# Power.net
KiCad netlist of a schematic drawn in Altium Designer
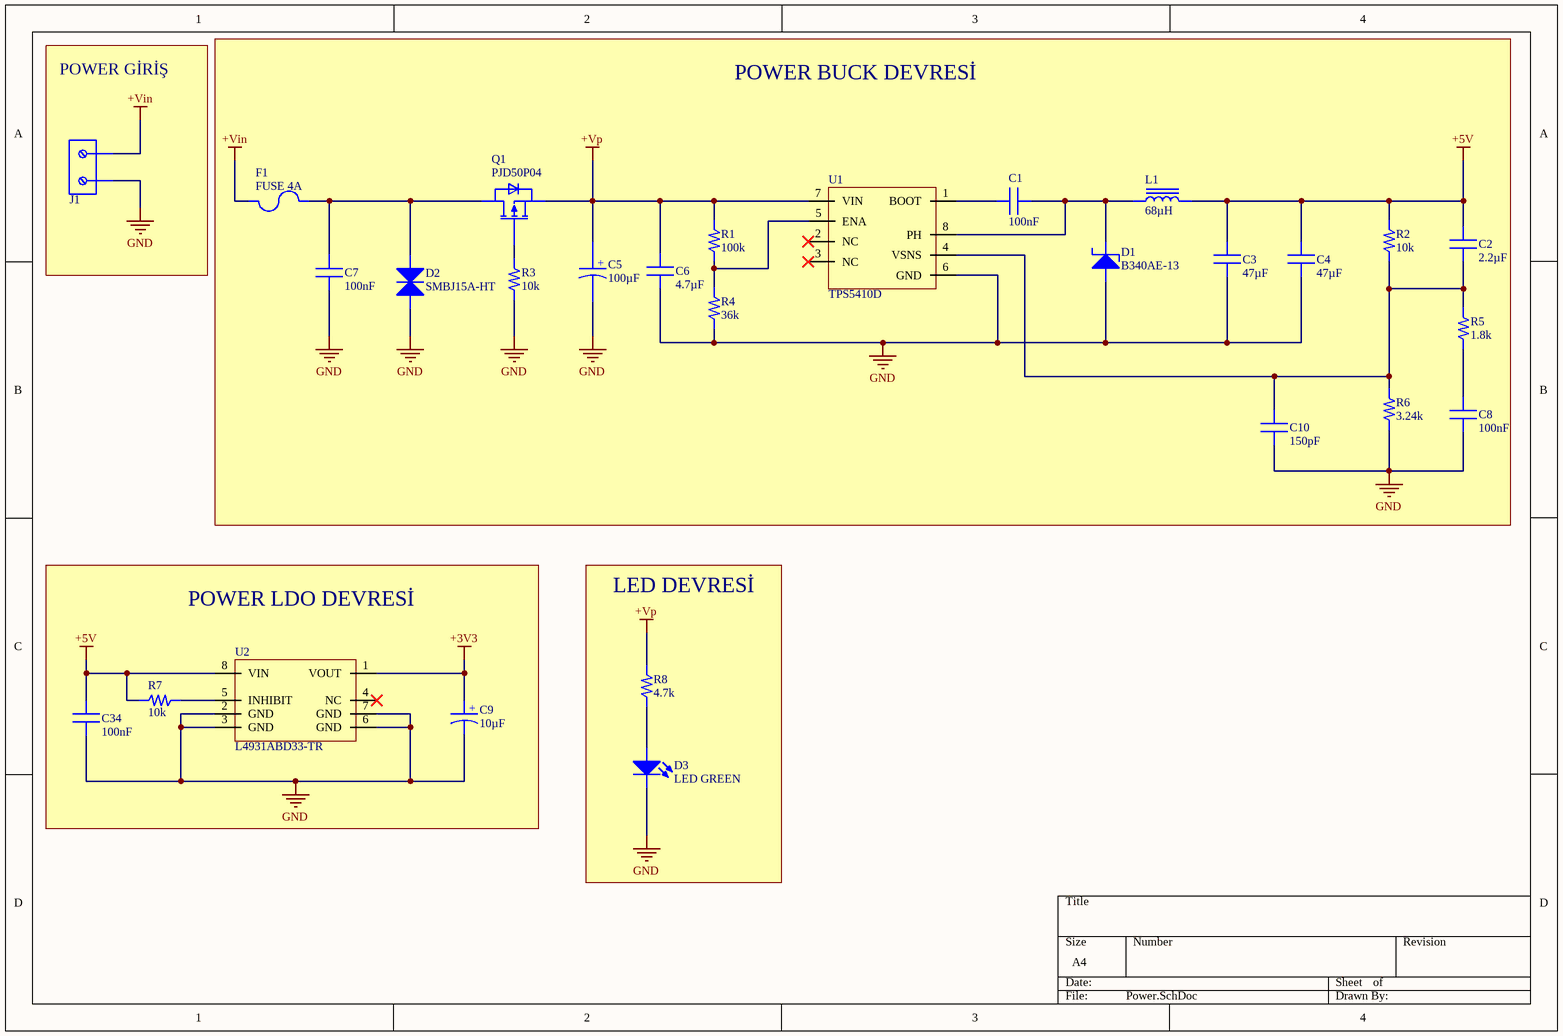
[diagram p0: Power.SchDoc]

(export (version "E")
  (design (tool "Eeschema 10.0.6"))
  (components
    (comp (ref "C1")
      (value "100nF")
      (footprint "CAP 0603 100NF")
      (description "MLCC (1608) 0603 100nF 50VDC ±10% X7R AUTOMOTIVE CL10B104KB85PNC")
      (fields (field (name "MANUFACTURER") "SAMSUNG") (field (name "TOLERANCE") "±10 %"))
      (libsource (lib "Motor Controller SchLib") (part "CAP 0603 100nF"))
    )
    (comp (ref "C2")
      (value "2.2µF")
      (footprint "CAP 0603 2.2uF")
      (description "MLCC (1608) 0603 2.2uF 16VDC ±10% X5R CL10A225KO8NNNC")
      (fields (field (name "TOLERANCE") "±10 %") (field (name "MANUFACTURER") "SAMSUNG"))
      (libsource (lib "Motor Controller SchLib") (part "CAP 0603 2.2uF"))
    )
    (comp (ref "C3")
      (value "47µF")
      (footprint "CL32A476KOJNNNE")
      (description "MLCC 1210 47uF 16VDC ±10% X5R   CL32A476KOJNNNE")
      (fields (field (name "MANUFACTURER") "SAMSUNG") (field (name "TOLERANCE") "±10 %"))
      (libsource (lib "Motor Controller SchLib") (part "CAP 1210 47µF"))
    )
    (comp (ref "C4")
      (value "47µF")
      (footprint "CL32A476KOJNNNE")
      (description "MLCC 1210 47uF 16VDC ±10% X5R   CL32A476KOJNNNE")
      (fields (field (name "MANUFACTURER") "SAMSUNG") (field (name "TOLERANCE") "±10 %"))
      (libsource (lib "Motor Controller SchLib") (part "CAP 1210 47µF"))
    )
    (comp (ref "C5")
      (value "100µF")
      (footprint "CAP_EEHZA1H101P")
      (description "CAP.EL.100µF 50V 10.5x10.5 105C SMD")
      (fields (field (name "MANUFACTURER") "Panasonic") (field (name "TOLERANCE") "±20 %"))
      (libsource (lib "Motor Controller SchLib") (part "CAP 100uF"))
    )
    (comp (ref "C6")
      (value "4.7µF")
      (footprint "CAP 0603 4.7uF")
      (description "MLCC (1608) 0603 4.7uF 35VDC ±10% X5R CL10A475KL8NRNC")
      (fields (field (name "MANUFACTURER") "SAMSUNG") (field (name "TOLERANCE") "±10 %"))
      (libsource (lib "Motor Controller SchLib") (part "CAP 0603 4.7uF CL10A475KL8NRNC"))
    )
    (comp (ref "C7")
      (value "100nF")
      (footprint "CAP 0603 100NF")
      (description "MLCC (1608) 0603 100nF 50VDC ±10% X7R AUTOMOTIVE CL10B104KB85PNC")
      (fields (field (name "MANUFACTURER") "SAMSUNG") (field (name "TOLERANCE") "±10 %"))
      (libsource (lib "Motor Controller SchLib") (part "CAP 0603 100nF"))
    )
    (comp (ref "C8")
      (value "100nF")
      (footprint "CAP 0603 100NF")
      (description "MLCC (1608) 0603 100nF 50VDC ±10% X7R AUTOMOTIVE CL10B104KB85PNC")
      (fields (field (name "MANUFACTURER") "SAMSUNG") (field (name "TOLERANCE") "±10 %"))
      (libsource (lib "Motor Controller SchLib") (part "CAP 0603 100nF"))
    )
    (comp (ref "C9")
      (value "10µF")
      (footprint "CAP_EEEFK1H100UR")
      (description "CAP.EL.10uF 50V 5x5.8 105C 2000H AEC-Q200 SMT")
      (fields (field (name "MANUFACTURER") "PANASONIC") (field (name "TOLERANCE") "±20 %"))
      (libsource (lib "Motor Controller SchLib") (part "CAP 10µF Electrolytic"))
    )
    (comp (ref "C10")
      (value "150pF")
      (footprint "CAP 0603 150pF")
      (description "MLCC (1608) 0603 150pF 50VDC ±5% C0G (NP0) CL10C151JB8NNNC")
      (fields (field (name "MANUFACTURER") "SAMSUNG") (field (name "TOLERANCE") "±5 %"))
      (libsource (lib "Motor Controller SchLib") (part "CAP 0603 150pF"))
    )
    (comp (ref "C34")
      (value "100nF")
      (footprint "CAP 0603 100NF")
      (description "MLCC (1608) 0603 100nF 50VDC ±10% X7R AUTOMOTIVE CL10B104KB85PNC")
      (fields (field (name "MANUFACTURER") "SAMSUNG") (field (name "TOLERANCE") "±10 %"))
      (libsource (lib "Motor Controller SchLib") (part "CAP 0603 100nF"))
    )
    (comp (ref "D1")
      (value "B340AE-13")
      (footprint "DIODE B340AE-13")
      (description "DIODE SCHOTTKY 3A 40V SMA DO-214AC")
      (fields (field (name "MANUFACTURER") "DIODES"))
      (libsource (lib "Motor Controller SchLib") (part "DIODE SCHOTTKY B340AE-13"))
    )
    (comp (ref "D2")
      (value "SMBJ15A-HT")
      (footprint "TVS DIODE SMBJ15A")
      (description "DIODE TVS 600W 15V DO214AA SMB")
      (fields (field (name "MANUFACTURER") "HOTTECH"))
      (libsource (lib "Motor Controller SchLib") (part "DIODE TVS SMBJ15A-HT"))
    )
    (comp (ref "D3")
      (value "LED GREEN")
      (footprint "LED GREEN 0603 APT1608CGCK")
      (description "LED GREEN CLEAR CHIP SMD")
      (fields (field (name "MANUFACTURER") "KINGBRIGHT"))
      (libsource (lib "Motor Controller SchLib") (part "SMD LED GREEN APT1608CGCK"))
    )
    (comp (ref "F1")
      (value "FUSE 4A")
      (footprint "FUSE 0805 MFU0805FF04000P100")
      (description "FUSE BOARD MOUNT 0805 4A 32VDC")
      (fields (field (name "MANUFACTURER") "VISHAY"))
      (libsource (lib "Motor Controller SchLib") (part "FUSE"))
    )
    (comp (ref "J1")
      (value "2x1 5mm T.B.")
      (footprint "Terminal Block 2x1")
      (description "TERM.BLK.5.00MM 2P PCB TYPE 0 BOY BLUE")
      (fields (field (name "MANUFACTURER") "DEGSON"))
      (libsource (lib "Motor Controller SchLib") (part "Terminal Block 2x1"))
    )
    (comp (ref "L1")
      (value "68µH")
      (footprint "IND CBC3225T680KR 68uH")
      (description "INDUCTOR FIXED 68UH 10x10mm SMD 744066680")
      (fields (field (name "TOLERANCE") "±30 %") (field (name "MANUFACTURER") "WURTH"))
      (libsource (lib "Motor Controller SchLib") (part "INDUCTOR 68µH SMD 744066680"))
    )
    (comp (ref "Q1")
      (value "PJD50P04")
      (footprint "TO252 (DPAK) IRFR024NTRPBF")
      (description "MOSFET DIS.50A 40V P-CH AUTOMOTIVE TO-252AA SMT")
      (fields (field (name "VOLTAGE") "40 V") (field (name "MANUFACTURER") "PANJIT"))
      (libsource (lib "Motor Controller SchLib") (part "P-CH Mosfet 40V 9A PJD50P04-AU_L2_000A1"))
    )
    (comp (ref "R1")
      (value "100k")
      (footprint "RES 0402 ROYALOHM GENERAL")
      (description "RES.(1005) 0402 100K Ohms 1% 1/16W 100PPM\r\n0402WGF1003TCE")
      (fields (field (name "POWER") "1/16 W") (field (name "TOLERANCE") "±5 %"))
      (libsource (lib "Motor Controller SchLib") (part "RES 0402 100k 0402WGF1003TCE"))
    )
    (comp (ref "R2")
      (value "10k")
      (footprint "RES 0402 ROYALOHM GENERAL")
      (description "RES.(1005) 0402 10K Ohms 5% 1/16W 100PPM 0402WGJ0103TCE")
      (fields (field (name "TOLERANCE") "%5") (field (name "MANUFACTURER") "ROYALOHM"))
      (libsource (lib "Motor Controller SchLib") (part "RES 0402 10k"))
    )
    (comp (ref "R3")
      (value "10k")
      (footprint "RES 0402 ROYALOHM GENERAL")
      (description "RES.(1005) 0402 10K Ohms 5% 1/16W 100PPM 0402WGJ0103TCE")
      (fields (field (name "TOLERANCE") "%5") (field (name "MANUFACTURER") "ROYALOHM"))
      (libsource (lib "Motor Controller SchLib") (part "RES 0402 10k"))
    )
    (comp (ref "R4")
      (value "36k")
      (footprint "RES 0402 ROYALOHM GENERAL")
      (description "RES.(1005) 0402 36K Ohms 1% 1/16W 100PPM 0402WGF3602TCE")
      (fields (field (name "POWER") "1/16 W-S") (field (name "TOLERANCE") "±1 %"))
      (libsource (lib "Motor Controller SchLib") (part "RES 0402 36k 0402WGF3602TCE"))
    )
    (comp (ref "R5")
      (value "1.8k")
      (footprint "RES 0402 ROYALOHM GENERAL")
      (description "RES.(1005) 0402 1.8K Ohms 5% 1/16W 100PPM 0402WGJ0182TCE")
      (fields (field (name "TOLERANCE") "±5 %") (field (name "MANUFACTURER") "ROYALOHM"))
      (libsource (lib "Motor Controller SchLib") (part "RES 0402 1.8k 0402WGJ0182TCE"))
    )
    (comp (ref "R6")
      (value "3.24k")
      (footprint "RES 0402 ROYALOHM GENERAL")
      (description "RES 0805 3.24k Ohms 1% 1/8W-S 100PPM 0402WGF3241TCE")
      (fields (field (name "POWER") "1/16 W-S") (field (name "TOLERANCE") "±1 %"))
      (libsource (lib "Motor Controller SchLib") (part "RES 0402 3.24k 0402WGF3241TCE"))
    )
    (comp (ref "R7")
      (value "10k")
      (footprint "RES 0402 ROYALOHM GENERAL")
      (description "RES.(1005) 0402 10K Ohms 5% 1/16W 100PPM 0402WGJ0103TCE")
      (fields (field (name "TOLERANCE") "%5") (field (name "MANUFACTURER") "ROYALOHM"))
      (libsource (lib "Motor Controller SchLib") (part "RES 0402 10k"))
    )
    (comp (ref "R8")
      (value "4.7k")
      (footprint "ROYALOHM 0603 RES")
      (description "RES.(1608) 0603 4.7K Ohms 5% 1/10W-S 100PPM 0603SAJ0472T5E")
      (fields (field (name "TOLERANCE") "±5 %") (field (name "POWER") "1/16W"))
      (libsource (lib "Motor Controller SchLib") (part "RES 0402 4.7k 0603SAJ0472T5E"))
    )
    (comp (ref "U1")
      (value "TPS5410D")
      (footprint "SOIC127TPS5410DR")
      (description "IC-5410DR REG BUCK ADJ 1A 8SOIC SMD TI")
      (fields (field (name "MANUFACTURER") "TEXAS TI"))
      (libsource (lib "Motor Controller SchLib") (part "Buck Converter TPS5410D"))
    )
    (comp (ref "U2")
      (value "L4931ABD33-TR")
      (footprint "LDO L4931ABD33-TR SOIC8")
      (description "IC REG LINEAR 3.3V 250MA 8SO L4931ABD33")
      (fields (field (name "MANUFACTURER") "STM"))
      (libsource (lib "Motor Controller SchLib") (part "LDO L4931ABD33"))
    )
  )
  (nets
    (net (code "1") (name "+3V3") (class "Default")
      (node (ref "C9") (pin "1") (pinfunction "1_1") (pintype "passive"))
      (node (ref "U2") (pin "1") (pinfunction "VOUT_1") (pintype "passive"))
    )
    (net (code "2") (name "+5V") (class "Default")
      (node (ref "C2") (pin "2") (pinfunction "2_2") (pintype "passive"))
      (node (ref "C3") (pin "2") (pinfunction "2_2") (pintype "passive"))
      (node (ref "C34") (pin "2") (pinfunction "2_2") (pintype "passive"))
      (node (ref "C4") (pin "2") (pinfunction "2_2") (pintype "passive"))
      (node (ref "L1") (pin "2") (pinfunction "2_2") (pintype "passive"))
      (node (ref "R2") (pin "2") (pinfunction "2_2") (pintype "passive"))
      (node (ref "R7") (pin "1") (pinfunction "1_1") (pintype "passive"))
      (node (ref "U2") (pin "8") (pinfunction "VIN_8") (pintype "passive"))
    )
    (net (code "3") (name "+Vin") (class "Default")
      (node (ref "F1") (pin "2") (pinfunction "2_2") (pintype "passive"))
      (node (ref "J1") (pin "1") (pinfunction "1_1") (pintype "power_in"))
    )
    (net (code "4") (name "+Vp") (class "Default")
      (node (ref "C5") (pin "1") (pinfunction "1_1") (pintype "passive"))
      (node (ref "C6") (pin "2") (pinfunction "2_2") (pintype "passive"))
      (node (ref "Q1") (pin "3") (pinfunction "Source_3") (pintype "passive"))
      (node (ref "R1") (pin "2") (pinfunction "2_2") (pintype "passive"))
      (node (ref "R8") (pin "2") (pinfunction "2_2") (pintype "passive"))
      (node (ref "U1") (pin "7") (pinfunction "VIN_7") (pintype "passive"))
    )
    (net (code "5") (name "GND") (class "Default")
      (node (ref "C10") (pin "1") (pinfunction "1_1") (pintype "passive"))
      (node (ref "C3") (pin "1") (pinfunction "1_1") (pintype "passive"))
      (node (ref "C34") (pin "1") (pinfunction "1_1") (pintype "passive"))
      (node (ref "C4") (pin "1") (pinfunction "1_1") (pintype "passive"))
      (node (ref "C5") (pin "2") (pinfunction "2_2") (pintype "passive"))
      (node (ref "C6") (pin "1") (pinfunction "1_1") (pintype "passive"))
      (node (ref "C7") (pin "1") (pinfunction "1_1") (pintype "passive"))
      (node (ref "C8") (pin "1") (pinfunction "1_1") (pintype "passive"))
      (node (ref "C9") (pin "2") (pinfunction "2_2") (pintype "passive"))
      (node (ref "D1") (pin "A") (pinfunction "Anode_A") (pintype "passive"))
      (node (ref "D2") (pin "1") (pinfunction "A_1") (pintype "passive"))
      (node (ref "D3") (pin "C") (pinfunction "Cathode_C") (pintype "passive"))
      (node (ref "J1") (pin "2") (pinfunction "2_2") (pintype "power_in"))
      (node (ref "R3") (pin "1") (pinfunction "1_1") (pintype "passive"))
      (node (ref "R4") (pin "1") (pinfunction "1_1") (pintype "passive"))
      (node (ref "R6") (pin "1") (pinfunction "1_1") (pintype "passive"))
      (node (ref "U1") (pin "6") (pinfunction "GND_6") (pintype "passive"))
      (node (ref "U2") (pin "2") (pinfunction "GND_2") (pintype "passive"))
      (node (ref "U2") (pin "3") (pinfunction "GND_3") (pintype "passive"))
      (node (ref "U2") (pin "6") (pinfunction "GND_6") (pintype "passive"))
      (node (ref "U2") (pin "7") (pinfunction "GND_7") (pintype "passive"))
    )
    (net (code "6") (name "Net-(C8-Pad2)") (class "Default")
      (node (ref "C8") (pin "2") (pinfunction "2_2") (pintype "passive"))
      (node (ref "R5") (pin "1") (pinfunction "1_1") (pintype "passive"))
    )
    (net (code "7") (name "Net-(D1-Cathode)") (class "Default")
      (node (ref "C1") (pin "2") (pinfunction "2_2") (pintype "passive"))
      (node (ref "D1") (pin "C") (pinfunction "Cathode_C") (pintype "passive"))
      (node (ref "L1") (pin "1") (pinfunction "1_1") (pintype "passive"))
      (node (ref "U1") (pin "8") (pinfunction "PH_8") (pintype "passive"))
    )
    (net (code "8") (name "Net-(D2-C)") (class "Default")
      (node (ref "C7") (pin "2") (pinfunction "2_2") (pintype "passive"))
      (node (ref "D2") (pin "2") (pinfunction "C_2") (pintype "passive"))
      (node (ref "F1") (pin "1") (pinfunction "1_1") (pintype "passive"))
      (node (ref "Q1") (pin "4") (pinfunction "Drain_4") (pintype "passive"))
    )
    (net (code "9") (name "Net-(D3-Anode)") (class "Default")
      (node (ref "D3") (pin "A") (pinfunction "Anode_A") (pintype "passive"))
      (node (ref "R8") (pin "1") (pinfunction "1_1") (pintype "passive"))
    )
    (net (code "10") (name "Net-(Q1-Gate)") (class "Default")
      (node (ref "Q1") (pin "1") (pinfunction "Gate_1") (pintype "passive"))
      (node (ref "R3") (pin "2") (pinfunction "2_2") (pintype "passive"))
    )
    (net (code "11") (name "Net-(U1-BOOT)") (class "Default")
      (node (ref "C1") (pin "1") (pinfunction "1_1") (pintype "passive"))
      (node (ref "U1") (pin "1") (pinfunction "BOOT_1") (pintype "passive"))
    )
    (net (code "12") (name "Net-(U1-ENA)") (class "Default")
      (node (ref "R1") (pin "1") (pinfunction "1_1") (pintype "passive"))
      (node (ref "R4") (pin "2") (pinfunction "2_2") (pintype "passive"))
      (node (ref "U1") (pin "5") (pinfunction "ENA_5") (pintype "passive"))
    )
    (net (code "13") (name "Net-(U1-VSNS)") (class "Default")
      (node (ref "C10") (pin "2") (pinfunction "2_2") (pintype "passive"))
      (node (ref "C2") (pin "1") (pinfunction "1_1") (pintype "passive"))
      (node (ref "R2") (pin "1") (pinfunction "1_1") (pintype "passive"))
      (node (ref "R5") (pin "2") (pinfunction "2_2") (pintype "passive"))
      (node (ref "R6") (pin "2") (pinfunction "2_2") (pintype "passive"))
      (node (ref "U1") (pin "4") (pinfunction "VSNS_4") (pintype "passive"))
    )
    (net (code "14") (name "Net-(U2-INHIBIT)") (class "Default")
      (node (ref "R7") (pin "2") (pinfunction "2_2") (pintype "passive"))
      (node (ref "U2") (pin "5") (pinfunction "INHIBIT_5") (pintype "passive"))
    )
    (net (code "15") (name "unconnected-(U1-NC-Pad2)") (class "Default")
      (node (ref "U1") (pin "2") (pinfunction "NC_2") (pintype "passive+no_connect"))
    )
    (net (code "16") (name "unconnected-(U1-NC-Pad3)") (class "Default")
      (node (ref "U1") (pin "3") (pinfunction "NC_3") (pintype "passive+no_connect"))
    )
    (net (code "17") (name "unconnected-(U2-NC-Pad4)") (class "Default")
      (node (ref "U2") (pin "4") (pinfunction "NC_4") (pintype "passive+no_connect"))
    )
  )
)
